# 258Verbos.net
KiCad netlist of a schematic drawn in EAGLE
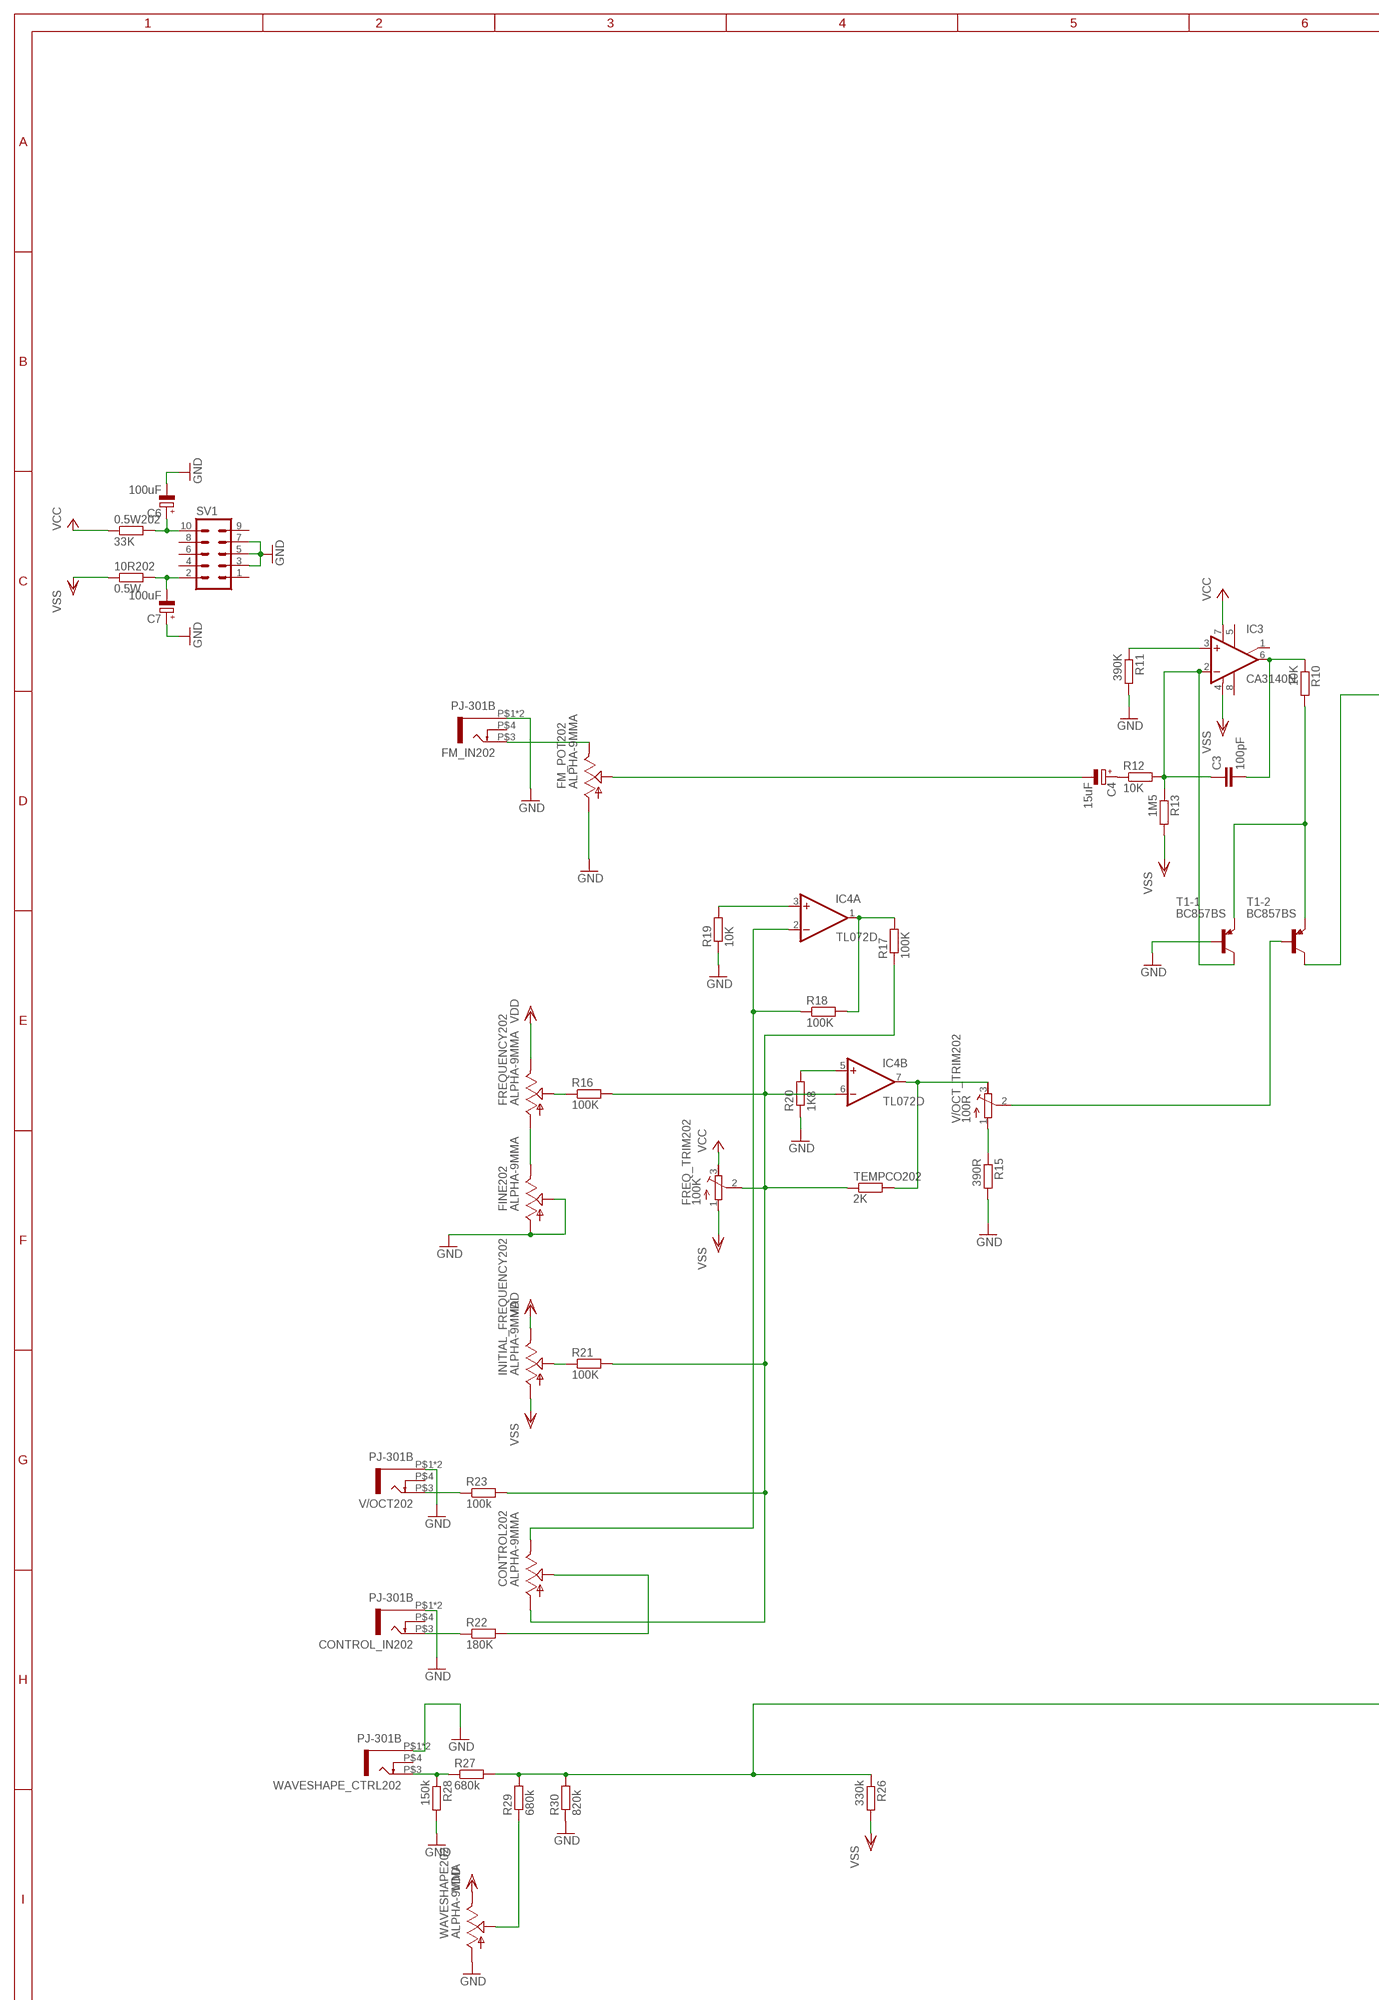
[diagram p0: schematic, sheet 1, part 1 of 2]
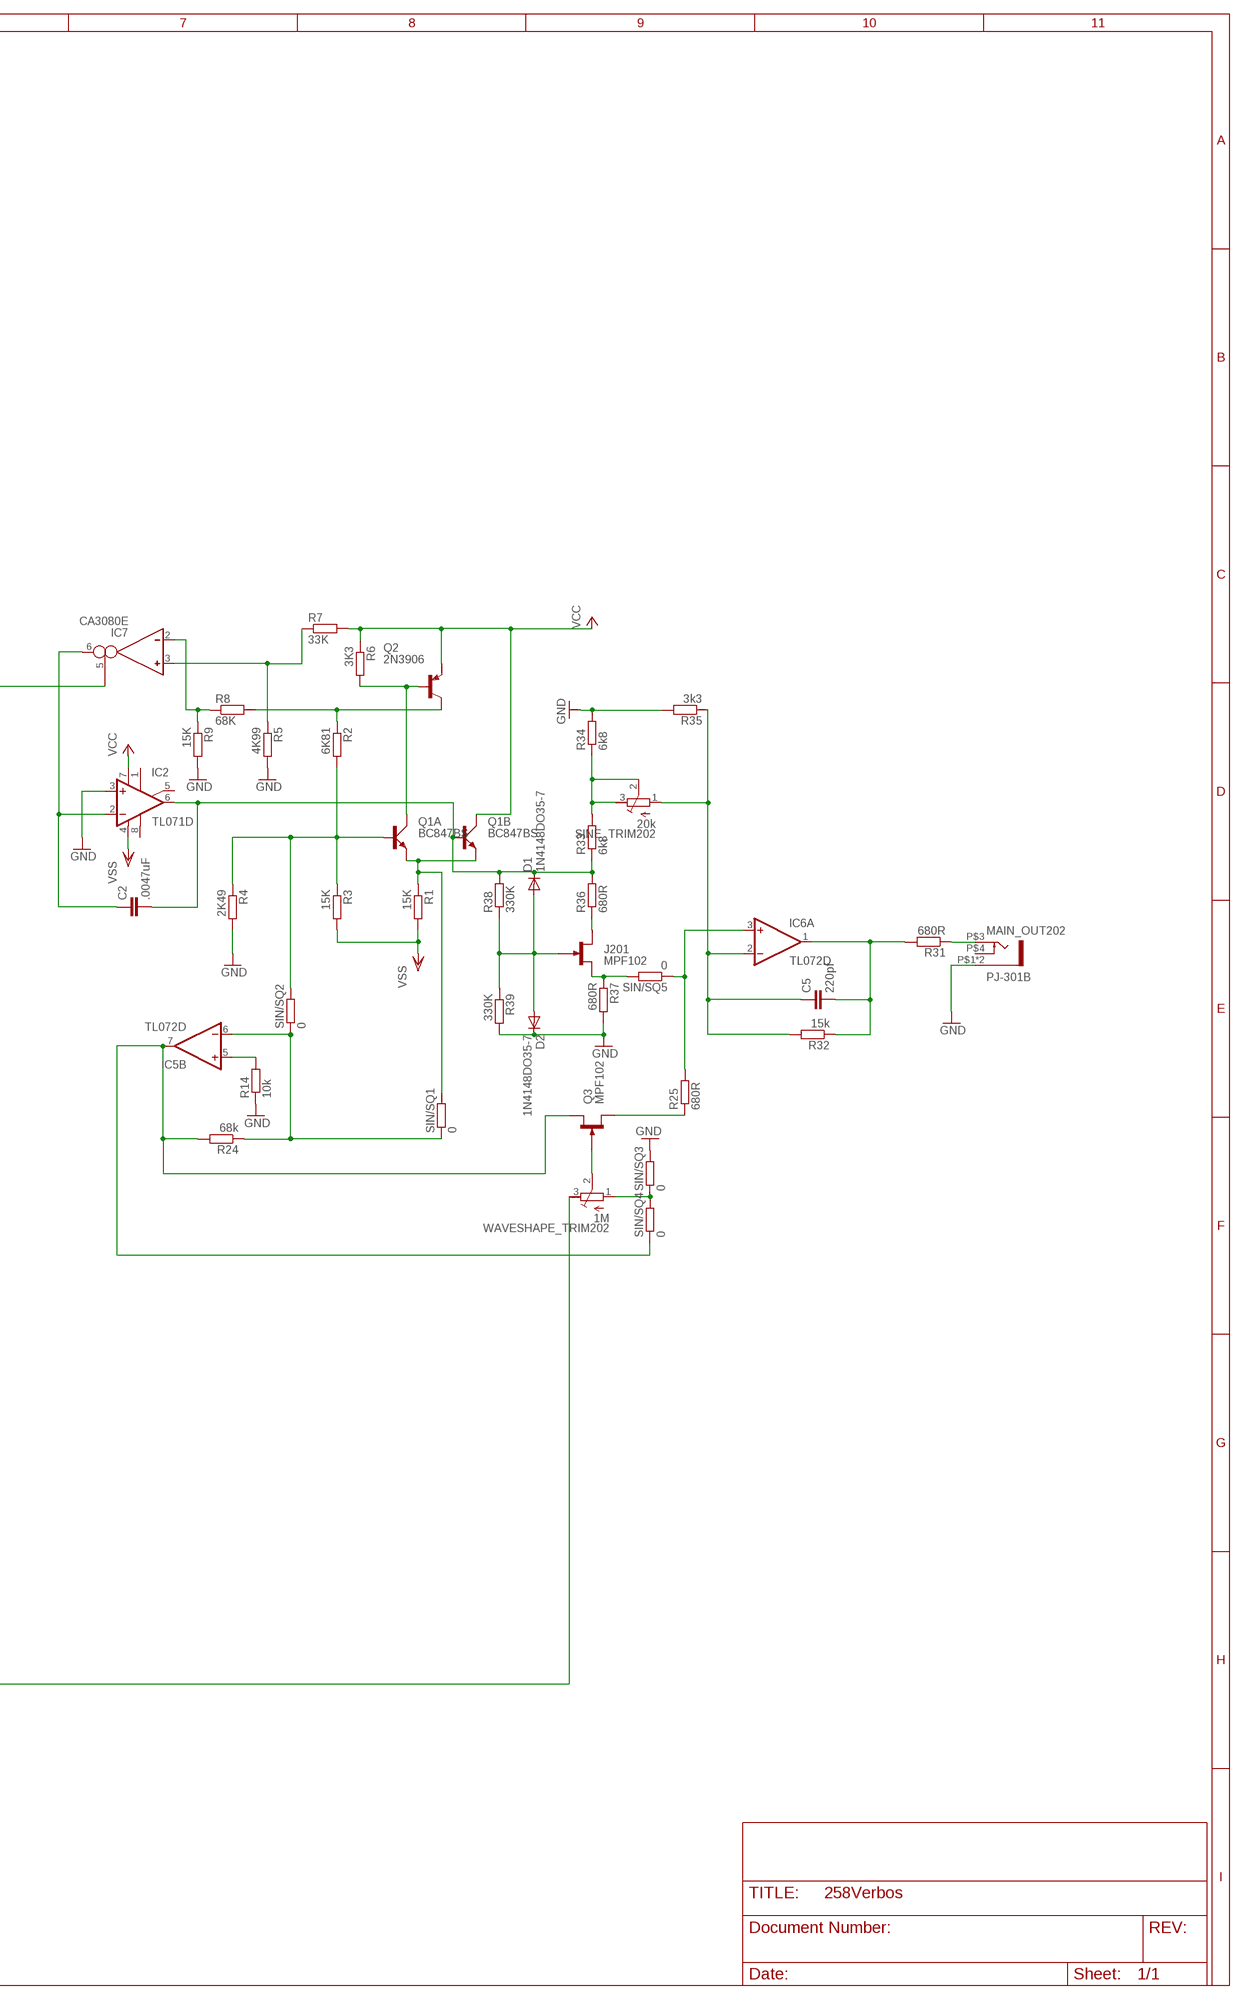
[diagram p1: schematic, sheet 1, part 2 of 2]

(export (version "E")
  (design (tool "Eeschema 10.0.6"))
  (components
    (comp (ref "0.5W202")
      (value "33K")
      (footprint "eagle-import:R0805")
      (libsource (lib "eagle-import") (part "R-EU_R0805"))
    )
    (comp (ref "10R202")
      (value "0.5W")
      (footprint "eagle-import:R0805")
      (libsource (lib "eagle-import") (part "R-EU_R0805"))
    )
    (comp (ref "C2")
      (value ".0047uF")
      (footprint "eagle-import:C5B4.5")
      (libsource (lib "eagle-import") (part "C5/4.5"))
    )
    (comp (ref "C3")
      (value "100pF")
      (footprint "eagle-import:C2.5-3")
      (libsource (lib "eagle-import") (part "C2,5-3"))
    )
    (comp (ref "C4")
      (value "15uF")
      (footprint "eagle-import:E2,5-6E")
      (libsource (lib "eagle-import") (part "CPOL-EUE2,5-6E"))
    )
    (comp (ref "C5")
      (value "220pf")
      (footprint "eagle-import:C2.5-3")
      (libsource (lib "eagle-import") (part "C2,5-3"))
    )
    (comp (ref "C6")
      (value "100uF")
      (footprint "eagle-import:E2,5-6E")
      (libsource (lib "eagle-import") (part "CPOL-EUE2,5-6E"))
    )
    (comp (ref "C7")
      (value "100uF")
      (footprint "eagle-import:E2,5-6E")
      (libsource (lib "eagle-import") (part "CPOL-EUE2,5-6E"))
    )
    (comp (ref "CONTROL202")
      (value "ALPHA-9MMA")
      (footprint "eagle-import:EVUF")
      (libsource (lib "eagle-import") (part "ALPHA-9MMA"))
    )
    (comp (ref "CONTROL_IN202")
      (value "PJ-301B")
      (footprint "eagle-import:PJ-301B")
      (libsource (lib "eagle-import") (part "PJ-301B"))
    )
    (comp (ref "D1")
      (value "1N4148DO35-7")
      (footprint "eagle-import:DO35-7")
      (libsource (lib "eagle-import") (part "1N4148DO35-7"))
    )
    (comp (ref "D2")
      (value "1N4148DO35-7")
      (footprint "eagle-import:DO35-7")
      (libsource (lib "eagle-import") (part "1N4148DO35-7"))
    )
    (comp (ref "FINE202")
      (value "ALPHA-9MMA")
      (footprint "eagle-import:EVUF")
      (libsource (lib "eagle-import") (part "ALPHA-9MMA"))
    )
    (comp (ref "FM_IN202")
      (value "PJ-301B")
      (footprint "eagle-import:PJ-301B")
      (libsource (lib "eagle-import") (part "PJ-301B"))
    )
    (comp (ref "FM_POT202")
      (value "ALPHA-9MMA")
      (footprint "eagle-import:EVUF")
      (libsource (lib "eagle-import") (part "ALPHA-9MMA"))
    )
    (comp (ref "FREQUENCY202")
      (value "ALPHA-9MMA")
      (footprint "eagle-import:EVUF")
      (libsource (lib "eagle-import") (part "ALPHA-9MMA"))
    )
    (comp (ref "FREQ_TRIM202")
      (value "100K")
      (footprint "eagle-import:RTRIM64W")
      (libsource (lib "eagle-import") (part "R-TRIMM64W"))
    )
    (comp (ref "IC2")
      (value "TL071D")
      (footprint "eagle-import:SO08")
      (libsource (lib "eagle-import") (part "TL071D"))
    )
    (comp (ref "IC3")
      (value "CA3140N")
      (footprint "eagle-import:DIL08")
      (libsource (lib "eagle-import") (part "CA3140N"))
    )
    (comp (ref "IC4")
      (value "TL072D")
      (footprint "eagle-import:SO08")
      (libsource (lib "eagle-import") (part "TL072D"))
    )
    (comp (ref "IC5")
      (value "TL072D")
      (footprint "eagle-import:SO08")
      (libsource (lib "eagle-import") (part "TL072D"))
    )
    (comp (ref "IC6")
      (value "TL072D")
      (footprint "eagle-import:SO08")
      (libsource (lib "eagle-import") (part "TL072D"))
    )
    (comp (ref "IC7")
      (value "CA3080E")
      (footprint "eagle-import:DIL08")
      (libsource (lib "eagle-import") (part "CA3080E"))
    )
    (comp (ref "INITIAL_FREQUENCY202")
      (value "ALPHA-9MMA")
      (footprint "eagle-import:EVUF")
      (libsource (lib "eagle-import") (part "ALPHA-9MMA"))
    )
    (comp (ref "J201")
      (value "MPF102")
      (footprint "eagle-import:TO92F")
      (libsource (lib "eagle-import") (part "MPF102"))
    )
    (comp (ref "MAIN_OUT202")
      (value "PJ-301B")
      (footprint "eagle-import:PJ-301B")
      (libsource (lib "eagle-import") (part "PJ-301B"))
    )
    (comp (ref "Q1")
      (value "BC847BS")
      (footprint "eagle-import:SOT363_PHILIPS")
      (libsource (lib "eagle-import") (part "BC847BS"))
    )
    (comp (ref "Q2")
      (value "2N3906")
      (footprint "eagle-import:TO92")
      (libsource (lib "eagle-import") (part "2N3906"))
    )
    (comp (ref "Q3")
      (value "MPF102")
      (footprint "eagle-import:TO92F")
      (libsource (lib "eagle-import") (part "MPF102"))
    )
    (comp (ref "R1")
      (value "15K")
      (footprint "eagle-import:R0805")
      (libsource (lib "eagle-import") (part "R-EU_R0805"))
    )
    (comp (ref "R2")
      (value "6K81")
      (footprint "eagle-import:R0805")
      (libsource (lib "eagle-import") (part "R-EU_R0805"))
    )
    (comp (ref "R3")
      (value "15K")
      (footprint "eagle-import:R0805")
      (libsource (lib "eagle-import") (part "R-EU_R0805"))
    )
    (comp (ref "R4")
      (value "2K49")
      (footprint "eagle-import:R0805")
      (libsource (lib "eagle-import") (part "R-EU_R0805"))
    )
    (comp (ref "R5")
      (value "4K99")
      (footprint "eagle-import:R0805")
      (libsource (lib "eagle-import") (part "R-EU_R0805"))
    )
    (comp (ref "R6")
      (value "3K3")
      (footprint "eagle-import:R0805")
      (libsource (lib "eagle-import") (part "R-EU_R0805"))
    )
    (comp (ref "R7")
      (value "33K")
      (footprint "eagle-import:R0805")
      (libsource (lib "eagle-import") (part "R-EU_R0805"))
    )
    (comp (ref "R8")
      (value "68K")
      (footprint "eagle-import:R0805")
      (libsource (lib "eagle-import") (part "R-EU_R0805"))
    )
    (comp (ref "R9")
      (value "15K")
      (footprint "eagle-import:R0805")
      (libsource (lib "eagle-import") (part "R-EU_R0805"))
    )
    (comp (ref "R10")
      (value "10K")
      (footprint "eagle-import:R0805")
      (libsource (lib "eagle-import") (part "R-EU_R0805"))
    )
    (comp (ref "R11")
      (value "390K")
      (footprint "eagle-import:R0805")
      (libsource (lib "eagle-import") (part "R-EU_R0805"))
    )
    (comp (ref "R12")
      (value "10K")
      (footprint "eagle-import:R0805")
      (libsource (lib "eagle-import") (part "R-EU_R0805"))
    )
    (comp (ref "R13")
      (value "1M5")
      (footprint "eagle-import:R0805")
      (libsource (lib "eagle-import") (part "R-EU_R0805"))
    )
    (comp (ref "R14")
      (value "10k")
      (footprint "eagle-import:R0805")
      (libsource (lib "eagle-import") (part "R-EU_R0805"))
    )
    (comp (ref "R15")
      (value "390R")
      (footprint "eagle-import:R0805")
      (libsource (lib "eagle-import") (part "R-EU_R0805"))
    )
    (comp (ref "R16")
      (value "100K")
      (footprint "eagle-import:R0805")
      (libsource (lib "eagle-import") (part "R-EU_R0805"))
    )
    (comp (ref "R17")
      (value "100K")
      (footprint "eagle-import:R0805")
      (libsource (lib "eagle-import") (part "R-EU_R0805"))
    )
    (comp (ref "R18")
      (value "100K")
      (footprint "eagle-import:R0805")
      (libsource (lib "eagle-import") (part "R-EU_R0805"))
    )
    (comp (ref "R19")
      (value "10K")
      (footprint "eagle-import:R0805")
      (libsource (lib "eagle-import") (part "R-EU_R0805"))
    )
    (comp (ref "R20")
      (value "1K8")
      (footprint "eagle-import:R0805")
      (libsource (lib "eagle-import") (part "R-EU_R0805"))
    )
    (comp (ref "R21")
      (value "100K")
      (footprint "eagle-import:R0805")
      (libsource (lib "eagle-import") (part "R-EU_R0805"))
    )
    (comp (ref "R22")
      (value "180K")
      (footprint "eagle-import:R0805")
      (libsource (lib "eagle-import") (part "R-EU_R0805"))
    )
    (comp (ref "R23")
      (value "100k")
      (footprint "eagle-import:R0805")
      (libsource (lib "eagle-import") (part "R-EU_R0805"))
    )
    (comp (ref "R24")
      (value "68k")
      (footprint "eagle-import:R0805")
      (libsource (lib "eagle-import") (part "R-EU_R0805"))
    )
    (comp (ref "R25")
      (value "680R")
      (footprint "eagle-import:R0805")
      (libsource (lib "eagle-import") (part "R-EU_R0805"))
    )
    (comp (ref "R26")
      (value "330k")
      (footprint "eagle-import:R0805")
      (libsource (lib "eagle-import") (part "R-EU_R0805"))
    )
    (comp (ref "R27")
      (value "680k")
      (footprint "eagle-import:R0805")
      (libsource (lib "eagle-import") (part "R-EU_R0805"))
    )
    (comp (ref "R28")
      (value "150k")
      (footprint "eagle-import:R0805")
      (libsource (lib "eagle-import") (part "R-EU_R0805"))
    )
    (comp (ref "R29")
      (value "680k")
      (footprint "eagle-import:R0805")
      (libsource (lib "eagle-import") (part "R-EU_R0805"))
    )
    (comp (ref "R30")
      (value "820k")
      (footprint "eagle-import:R0805")
      (libsource (lib "eagle-import") (part "R-EU_R0805"))
    )
    (comp (ref "R31")
      (value "680R")
      (footprint "eagle-import:R0805")
      (libsource (lib "eagle-import") (part "R-EU_R0805"))
    )
    (comp (ref "R32")
      (value "15k")
      (footprint "eagle-import:R0805")
      (libsource (lib "eagle-import") (part "R-EU_R0805"))
    )
    (comp (ref "R33")
      (value "6k8")
      (footprint "eagle-import:R0805")
      (libsource (lib "eagle-import") (part "R-EU_R0805"))
    )
    (comp (ref "R34")
      (value "6k8")
      (footprint "eagle-import:R0805")
      (libsource (lib "eagle-import") (part "R-EU_R0805"))
    )
    (comp (ref "R35")
      (value "3k3")
      (footprint "eagle-import:R0805")
      (libsource (lib "eagle-import") (part "R-EU_R0805"))
    )
    (comp (ref "R36")
      (value "680R")
      (footprint "eagle-import:R0805")
      (libsource (lib "eagle-import") (part "R-EU_R0805"))
    )
    (comp (ref "R37")
      (value "680R")
      (footprint "eagle-import:R0805")
      (libsource (lib "eagle-import") (part "R-EU_R0805"))
    )
    (comp (ref "R38")
      (value "330K")
      (footprint "eagle-import:R0805")
      (libsource (lib "eagle-import") (part "R-EU_R0805"))
    )
    (comp (ref "R39")
      (value "330K")
      (footprint "eagle-import:R0805")
      (libsource (lib "eagle-import") (part "R-EU_R0805"))
    )
    (comp (ref "SIN/SQ1")
      (value "0")
      (footprint "eagle-import:R0805")
      (libsource (lib "eagle-import") (part "R-EU_R0805"))
    )
    (comp (ref "SIN/SQ2")
      (value "0")
      (footprint "eagle-import:R0805")
      (libsource (lib "eagle-import") (part "R-EU_R0805"))
    )
    (comp (ref "SIN/SQ3")
      (value "0")
      (footprint "eagle-import:R0805")
      (libsource (lib "eagle-import") (part "R-EU_R0805"))
    )
    (comp (ref "SIN/SQ4")
      (value "0")
      (footprint "eagle-import:R0805")
      (libsource (lib "eagle-import") (part "R-EU_R0805"))
    )
    (comp (ref "SIN/SQ5")
      (value "0")
      (footprint "eagle-import:R0805")
      (libsource (lib "eagle-import") (part "R-EU_R0805"))
    )
    (comp (ref "SINE_TRIM202")
      (value "20k")
      (footprint "eagle-import:RTRIM64W")
      (libsource (lib "eagle-import") (part "R-TRIMM64W"))
    )
    (comp (ref "SV1")
      (value "10_PIN_HEADER")
      (footprint "eagle-import:MA05-2")
      (libsource (lib "eagle-import") (part "10_PIN_HEADER"))
    )
    (comp (ref "T1")
      (value "BC857BS")
      (footprint "eagle-import:SOT363")
      (libsource (lib "eagle-import") (part "BC857BS"))
    )
    (comp (ref "TEMPCO202")
      (value "2K")
      (footprint "eagle-import:R0805")
      (libsource (lib "eagle-import") (part "R-EU_R0805"))
    )
    (comp (ref "V/OCT202")
      (value "PJ-301B")
      (footprint "eagle-import:PJ-301B")
      (libsource (lib "eagle-import") (part "PJ-301B"))
    )
    (comp (ref "V/OCT_TRIM202")
      (value "100R")
      (footprint "eagle-import:RTRIM64W")
      (libsource (lib "eagle-import") (part "R-TRIMM64W"))
    )
    (comp (ref "WAVESHAPE202")
      (value "ALPHA-9MMA")
      (footprint "eagle-import:EVUF")
      (libsource (lib "eagle-import") (part "ALPHA-9MMA"))
    )
    (comp (ref "WAVESHAPE_CTRL202")
      (value "PJ-301B")
      (footprint "eagle-import:PJ-301B")
      (libsource (lib "eagle-import") (part "PJ-301B"))
    )
    (comp (ref "WAVESHAPE_TRIM202")
      (value "1M")
      (footprint "eagle-import:RTRIM64W")
      (libsource (lib "eagle-import") (part "R-TRIMM64W"))
    )
  )
  (nets
    (net (code "1") (name "GND") (class "Default")
      (node (ref "C6") (pin "-") (pinfunction "-_-") (pintype "passive"))
      (node (ref "C7") (pin "+") (pinfunction "+_+") (pintype "passive"))
      (node (ref "CONTROL_IN202") (pin "P$1") (pinfunction "5_P$1") (pintype "passive"))
      (node (ref "CONTROL_IN202") (pin "P$2") (pinfunction "5_P$2") (pintype "passive"))
      (node (ref "D2") (pin "C") (pinfunction "C_C") (pintype "passive"))
      (node (ref "FINE202") (pin "1") (pinfunction "A_1") (pintype "passive"))
      (node (ref "FINE202") (pin "2") (pinfunction "S_2") (pintype "passive"))
      (node (ref "FM_IN202") (pin "P$1") (pinfunction "5_P$1") (pintype "passive"))
      (node (ref "FM_IN202") (pin "P$2") (pinfunction "5_P$2") (pintype "passive"))
      (node (ref "FM_POT202") (pin "1") (pinfunction "A_1") (pintype "passive"))
      (node (ref "IC2") (pin "3") (pinfunction "+IN_3") (pintype "input"))
      (node (ref "MAIN_OUT202") (pin "P$1") (pinfunction "5_P$1") (pintype "passive"))
      (node (ref "MAIN_OUT202") (pin "P$2") (pinfunction "5_P$2") (pintype "passive"))
      (node (ref "R11") (pin "2") (pinfunction "2_2") (pintype "passive"))
      (node (ref "R14") (pin "1") (pinfunction "1_1") (pintype "passive"))
      (node (ref "R15") (pin "2") (pinfunction "2_2") (pintype "passive"))
      (node (ref "R19") (pin "1") (pinfunction "1_1") (pintype "passive"))
      (node (ref "R20") (pin "1") (pinfunction "1_1") (pintype "passive"))
      (node (ref "R28") (pin "2") (pinfunction "2_2") (pintype "passive"))
      (node (ref "R30") (pin "1") (pinfunction "1_1") (pintype "passive"))
      (node (ref "R34") (pin "2") (pinfunction "2_2") (pintype "passive"))
      (node (ref "R35") (pin "2") (pinfunction "2_2") (pintype "passive"))
      (node (ref "R37") (pin "2") (pinfunction "2_2") (pintype "passive"))
      (node (ref "R39") (pin "2") (pinfunction "2_2") (pintype "passive"))
      (node (ref "R4") (pin "2") (pinfunction "2_2") (pintype "passive"))
      (node (ref "R5") (pin "2") (pinfunction "2_2") (pintype "passive"))
      (node (ref "R9") (pin "2") (pinfunction "2_2") (pintype "passive"))
      (node (ref "SIN/SQ3") (pin "2") (pinfunction "2_2") (pintype "passive"))
      (node (ref "SV1") (pin "3") (pinfunction "3_3") (pintype "passive"))
      (node (ref "SV1") (pin "5") (pinfunction "5_5") (pintype "passive"))
      (node (ref "SV1") (pin "7") (pinfunction "7_7") (pintype "passive"))
      (node (ref "T1") (pin "2") (pinfunction "B_2") (pintype "passive"))
      (node (ref "V/OCT202") (pin "P$1") (pinfunction "5_P$1") (pintype "passive"))
      (node (ref "V/OCT202") (pin "P$2") (pinfunction "5_P$2") (pintype "passive"))
      (node (ref "WAVESHAPE202") (pin "1") (pinfunction "A_1") (pintype "passive"))
      (node (ref "WAVESHAPE_CTRL202") (pin "P$1") (pinfunction "5_P$1") (pintype "passive"))
      (node (ref "WAVESHAPE_CTRL202") (pin "P$2") (pinfunction "5_P$2") (pintype "passive"))
    )
    (net (code "2") (name "Net-(0.5W202-Pad2)") (class "Default")
      (node (ref "0.5W202") (pin "2") (pinfunction "2_2") (pintype "passive"))
      (node (ref "C6") (pin "+") (pinfunction "+_+") (pintype "passive"))
      (node (ref "SV1") (pin "10") (pinfunction "10_10") (pintype "passive"))
    )
    (net (code "3") (name "Net-(10R202-Pad2)") (class "Default")
      (node (ref "10R202") (pin "2") (pinfunction "2_2") (pintype "passive"))
      (node (ref "C7") (pin "-") (pinfunction "-_-") (pintype "passive"))
      (node (ref "SV1") (pin "2") (pinfunction "2_2") (pintype "passive"))
    )
    (net (code "4") (name "Net-(C4-Pad+)") (class "Default")
      (node (ref "C4") (pin "+") (pinfunction "+_+") (pintype "passive"))
      (node (ref "R12") (pin "1") (pinfunction "1_1") (pintype "passive"))
    )
    (net (code "5") (name "Net-(CONTROL202-A)") (class "Default")
      (node (ref "CONTROL202") (pin "1") (pinfunction "A_1") (pintype "passive"))
      (node (ref "FREQ_TRIM202") (pin "2") (pinfunction "S_2") (pintype "passive"))
      (node (ref "IC4") (pin "6") (pinfunction "-IN_6") (pintype "input"))
      (node (ref "R16") (pin "2") (pinfunction "2_2") (pintype "passive"))
      (node (ref "R17") (pin "1") (pinfunction "1_1") (pintype "passive"))
      (node (ref "R21") (pin "2") (pinfunction "2_2") (pintype "passive"))
      (node (ref "R23") (pin "2") (pinfunction "2_2") (pintype "passive"))
      (node (ref "TEMPCO202") (pin "1") (pinfunction "1_1") (pintype "passive"))
    )
    (net (code "6") (name "Net-(CONTROL202-E)") (class "Default")
      (node (ref "CONTROL202") (pin "3") (pinfunction "E_3") (pintype "passive"))
      (node (ref "IC4") (pin "2") (pinfunction "-IN_2") (pintype "input"))
      (node (ref "R18") (pin "1") (pinfunction "1_1") (pintype "passive"))
    )
    (net (code "7") (name "Net-(CONTROL202-S)") (class "Default")
      (node (ref "CONTROL202") (pin "2") (pinfunction "S_2") (pintype "passive"))
      (node (ref "R22") (pin "2") (pinfunction "2_2") (pintype "passive"))
    )
    (net (code "8") (name "Net-(CONTROL_IN202-3)") (class "Default")
      (node (ref "CONTROL_IN202") (pin "P$3") (pinfunction "3_P$3") (pintype "passive"))
      (node (ref "R22") (pin "1") (pinfunction "1_1") (pintype "passive"))
    )
    (net (code "9") (name "Net-(FINE202-E)") (class "Default")
      (node (ref "FINE202") (pin "3") (pinfunction "E_3") (pintype "passive"))
      (node (ref "FREQUENCY202") (pin "1") (pinfunction "A_1") (pintype "passive"))
    )
    (net (code "10") (name "Net-(FM_IN202-3)") (class "Default")
      (node (ref "FM_IN202") (pin "P$3") (pinfunction "3_P$3") (pintype "passive"))
      (node (ref "FM_POT202") (pin "3") (pinfunction "E_3") (pintype "passive"))
    )
    (net (code "11") (name "Net-(FM_POT202-S)") (class "Default")
      (node (ref "C4") (pin "-") (pinfunction "-_-") (pintype "passive"))
      (node (ref "FM_POT202") (pin "2") (pinfunction "S_2") (pintype "passive"))
    )
    (net (code "12") (name "Net-(FREQUENCY202-S)") (class "Default")
      (node (ref "FREQUENCY202") (pin "2") (pinfunction "S_2") (pintype "passive"))
      (node (ref "R16") (pin "1") (pinfunction "1_1") (pintype "passive"))
    )
    (net (code "13") (name "Net-(IC2--IN)") (class "Default")
      (node (ref "C2") (pin "1") (pinfunction "1_1") (pintype "passive"))
      (node (ref "IC2") (pin "2") (pinfunction "-IN_2") (pintype "input"))
      (node (ref "IC7") (pin "6") (pinfunction "OUT_6") (pintype "output"))
    )
    (net (code "14") (name "Net-(IC2-OUT)") (class "Default")
      (node (ref "C2") (pin "2") (pinfunction "2_2") (pintype "passive"))
      (node (ref "D1") (pin "C") (pinfunction "C_C") (pintype "passive"))
      (node (ref "IC2") (pin "6") (pinfunction "OUT_6") (pintype "output"))
      (node (ref "Q1") (pin "5") (pinfunction "B_5") (pintype "passive"))
      (node (ref "R33") (pin "1") (pinfunction "1_1") (pintype "passive"))
      (node (ref "R36") (pin "2") (pinfunction "2_2") (pintype "passive"))
      (node (ref "R38") (pin "2") (pinfunction "2_2") (pintype "passive"))
    )
    (net (code "15") (name "Net-(IC3-+IN)") (class "Default")
      (node (ref "IC3") (pin "3") (pinfunction "+IN_3") (pintype "input"))
      (node (ref "R11") (pin "1") (pinfunction "1_1") (pintype "passive"))
    )
    (net (code "16") (name "Net-(IC3--IN)") (class "Default")
      (node (ref "C3") (pin "1") (pinfunction "1_1") (pintype "passive"))
      (node (ref "IC3") (pin "2") (pinfunction "-IN_2") (pintype "input"))
      (node (ref "R12") (pin "2") (pinfunction "2_2") (pintype "passive"))
      (node (ref "R13") (pin "1") (pinfunction "1_1") (pintype "passive"))
      (node (ref "T1") (pin "6") (pinfunction "C_6") (pintype "passive"))
    )
    (net (code "17") (name "Net-(IC3-OUT)") (class "Default")
      (node (ref "C3") (pin "2") (pinfunction "2_2") (pintype "passive"))
      (node (ref "IC3") (pin "6") (pinfunction "OUT_6") (pintype "output"))
      (node (ref "R10") (pin "1") (pinfunction "1_1") (pintype "passive"))
    )
    (net (code "18") (name "Net-(IC4A-+IN)") (class "Default")
      (node (ref "IC4") (pin "3") (pinfunction "+IN_3") (pintype "input"))
      (node (ref "R19") (pin "2") (pinfunction "2_2") (pintype "passive"))
    )
    (net (code "19") (name "Net-(IC4A-OUT)") (class "Default")
      (node (ref "IC4") (pin "1") (pinfunction "OUT_1") (pintype "output"))
      (node (ref "R17") (pin "2") (pinfunction "2_2") (pintype "passive"))
      (node (ref "R18") (pin "2") (pinfunction "2_2") (pintype "passive"))
    )
    (net (code "20") (name "Net-(IC4B-+IN)") (class "Default")
      (node (ref "IC4") (pin "5") (pinfunction "+IN_5") (pintype "input"))
      (node (ref "R20") (pin "2") (pinfunction "2_2") (pintype "passive"))
    )
    (net (code "21") (name "Net-(IC4B-OUT)") (class "Default")
      (node (ref "IC4") (pin "7") (pinfunction "OUT_7") (pintype "output"))
      (node (ref "TEMPCO202") (pin "2") (pinfunction "2_2") (pintype "passive"))
      (node (ref "V/OCT_TRIM202") (pin "3") (pinfunction "E_3") (pintype "passive"))
    )
    (net (code "22") (name "Net-(IC5B-+IN)") (class "Default")
      (node (ref "IC5") (pin "5") (pinfunction "+IN_5") (pintype "input"))
      (node (ref "R14") (pin "2") (pinfunction "2_2") (pintype "passive"))
    )
    (net (code "23") (name "Net-(IC5B--IN)") (class "Default")
      (node (ref "IC5") (pin "6") (pinfunction "-IN_6") (pintype "input"))
      (node (ref "R24") (pin "1") (pinfunction "1_1") (pintype "passive"))
      (node (ref "SIN/SQ1") (pin "1") (pinfunction "1_1") (pintype "passive"))
      (node (ref "SIN/SQ2") (pin "1") (pinfunction "1_1") (pintype "passive"))
    )
    (net (code "24") (name "Net-(IC5B-OUT)") (class "Default")
      (node (ref "IC5") (pin "7") (pinfunction "OUT_7") (pintype "output"))
      (node (ref "Q3") (pin "1") (pinfunction "D_1") (pintype "passive"))
      (node (ref "R24") (pin "2") (pinfunction "2_2") (pintype "passive"))
      (node (ref "SIN/SQ4") (pin "1") (pinfunction "1_1") (pintype "passive"))
    )
    (net (code "25") (name "Net-(IC6A-+IN)") (class "Default")
      (node (ref "IC6") (pin "3") (pinfunction "+IN_3") (pintype "input"))
      (node (ref "R25") (pin "2") (pinfunction "2_2") (pintype "passive"))
      (node (ref "SIN/SQ5") (pin "1") (pinfunction "1_1") (pintype "passive"))
    )
    (net (code "26") (name "Net-(IC6A--IN)") (class "Default")
      (node (ref "C5") (pin "1") (pinfunction "1_1") (pintype "passive"))
      (node (ref "IC6") (pin "2") (pinfunction "-IN_2") (pintype "input"))
      (node (ref "R32") (pin "2") (pinfunction "2_2") (pintype "passive"))
      (node (ref "R35") (pin "1") (pinfunction "1_1") (pintype "passive"))
      (node (ref "SINE_TRIM202") (pin "1") (pinfunction "A_1") (pintype "passive"))
    )
    (net (code "27") (name "Net-(IC6A-OUT)") (class "Default")
      (node (ref "C5") (pin "2") (pinfunction "2_2") (pintype "passive"))
      (node (ref "IC6") (pin "1") (pinfunction "OUT_1") (pintype "output"))
      (node (ref "R31") (pin "2") (pinfunction "2_2") (pintype "passive"))
      (node (ref "R32") (pin "1") (pinfunction "1_1") (pintype "passive"))
    )
    (net (code "28") (name "Net-(IC7A-IN_N)") (class "Default")
      (node (ref "IC7") (pin "2") (pinfunction "IN_N_2") (pintype "input"))
      (node (ref "R8") (pin "1") (pinfunction "1_1") (pintype "passive"))
      (node (ref "R9") (pin "1") (pinfunction "1_1") (pintype "passive"))
    )
    (net (code "29") (name "Net-(IC7A-IN_P)") (class "Default")
      (node (ref "IC7") (pin "3") (pinfunction "IN_P_3") (pintype "input"))
      (node (ref "R5") (pin "1") (pinfunction "1_1") (pintype "passive"))
      (node (ref "R7") (pin "1") (pinfunction "1_1") (pintype "passive"))
    )
    (net (code "30") (name "Net-(IC7A-I_BIAS)") (class "Default")
      (node (ref "IC7") (pin "5") (pinfunction "I_BIAS_5") (pintype "input"))
      (node (ref "T1") (pin "3") (pinfunction "C_3") (pintype "passive"))
    )
    (net (code "31") (name "Net-(INITIAL_FREQUENCY202-S)") (class "Default")
      (node (ref "INITIAL_FREQUENCY202") (pin "2") (pinfunction "S_2") (pintype "passive"))
      (node (ref "R21") (pin "1") (pinfunction "1_1") (pintype "passive"))
    )
    (net (code "32") (name "Net-(J201-D)") (class "Default")
      (node (ref "J201") (pin "1") (pinfunction "D_1") (pintype "passive"))
      (node (ref "R36") (pin "1") (pinfunction "1_1") (pintype "passive"))
    )
    (net (code "33") (name "Net-(J201-G)") (class "Default")
      (node (ref "D1") (pin "A") (pinfunction "A_A") (pintype "passive"))
      (node (ref "D2") (pin "A") (pinfunction "A_A") (pintype "passive"))
      (node (ref "J201") (pin "3") (pinfunction "G_3") (pintype "passive"))
      (node (ref "R38") (pin "1") (pinfunction "1_1") (pintype "passive"))
      (node (ref "R39") (pin "1") (pinfunction "1_1") (pintype "passive"))
    )
    (net (code "34") (name "Net-(J201-S)") (class "Default")
      (node (ref "J201") (pin "2") (pinfunction "S_2") (pintype "passive"))
      (node (ref "R37") (pin "1") (pinfunction "1_1") (pintype "passive"))
      (node (ref "SIN/SQ5") (pin "2") (pinfunction "2_2") (pintype "passive"))
    )
    (net (code "35") (name "Net-(MAIN_OUT202-3)") (class "Default")
      (node (ref "MAIN_OUT202") (pin "P$3") (pinfunction "3_P$3") (pintype "passive"))
      (node (ref "R31") (pin "1") (pinfunction "1_1") (pintype "passive"))
    )
    (net (code "36") (name "Net-(Q1A-B)") (class "Default")
      (node (ref "Q1") (pin "2") (pinfunction "B_2") (pintype "passive"))
      (node (ref "R2") (pin "2") (pinfunction "2_2") (pintype "passive"))
      (node (ref "R3") (pin "1") (pinfunction "1_1") (pintype "passive"))
      (node (ref "R4") (pin "1") (pinfunction "1_1") (pintype "passive"))
      (node (ref "SIN/SQ2") (pin "2") (pinfunction "2_2") (pintype "passive"))
    )
    (net (code "37") (name "Net-(Q1A-C)") (class "Default")
      (node (ref "Q1") (pin "6") (pinfunction "C_6") (pintype "passive"))
      (node (ref "Q2") (pin "2") (pinfunction "B_2") (pintype "passive"))
      (node (ref "R6") (pin "2") (pinfunction "2_2") (pintype "passive"))
    )
    (net (code "38") (name "Net-(Q1A-E)") (class "Default")
      (node (ref "Q1") (pin "1") (pinfunction "E_1") (pintype "passive"))
      (node (ref "Q1") (pin "4") (pinfunction "E_4") (pintype "passive"))
      (node (ref "R1") (pin "1") (pinfunction "1_1") (pintype "passive"))
      (node (ref "SIN/SQ1") (pin "2") (pinfunction "2_2") (pintype "passive"))
    )
    (net (code "39") (name "Net-(Q2-C)") (class "Default")
      (node (ref "Q2") (pin "1") (pinfunction "C_1") (pintype "passive"))
      (node (ref "R2") (pin "1") (pinfunction "1_1") (pintype "passive"))
      (node (ref "R8") (pin "2") (pinfunction "2_2") (pintype "passive"))
    )
    (net (code "40") (name "Net-(Q3-G)") (class "Default")
      (node (ref "Q3") (pin "3") (pinfunction "G_3") (pintype "passive"))
      (node (ref "WAVESHAPE_TRIM202") (pin "2") (pinfunction "S_2") (pintype "passive"))
    )
    (net (code "41") (name "Net-(Q3-S)") (class "Default")
      (node (ref "Q3") (pin "2") (pinfunction "S_2") (pintype "passive"))
      (node (ref "R25") (pin "1") (pinfunction "1_1") (pintype "passive"))
    )
    (net (code "42") (name "Net-(SINE_TRIM202-E)") (class "Default")
      (node (ref "R33") (pin "2") (pinfunction "2_2") (pintype "passive"))
      (node (ref "R34") (pin "1") (pinfunction "1_1") (pintype "passive"))
      (node (ref "SINE_TRIM202") (pin "2") (pinfunction "S_2") (pintype "passive"))
      (node (ref "SINE_TRIM202") (pin "3") (pinfunction "E_3") (pintype "passive"))
    )
    (net (code "43") (name "Net-(T1A-E)") (class "Default")
      (node (ref "R10") (pin "2") (pinfunction "2_2") (pintype "passive"))
      (node (ref "T1") (pin "1") (pinfunction "E_1") (pintype "passive"))
      (node (ref "T1") (pin "4") (pinfunction "E_4") (pintype "passive"))
    )
    (net (code "44") (name "Net-(T1B-B)") (class "Default")
      (node (ref "T1") (pin "5") (pinfunction "B_5") (pintype "passive"))
      (node (ref "V/OCT_TRIM202") (pin "2") (pinfunction "S_2") (pintype "passive"))
    )
    (net (code "45") (name "Net-(V/OCT202-3)") (class "Default")
      (node (ref "R23") (pin "1") (pinfunction "1_1") (pintype "passive"))
      (node (ref "V/OCT202") (pin "P$3") (pinfunction "3_P$3") (pintype "passive"))
    )
    (net (code "46") (name "Net-(V/OCT_TRIM202-A)") (class "Default")
      (node (ref "R15") (pin "1") (pinfunction "1_1") (pintype "passive"))
      (node (ref "V/OCT_TRIM202") (pin "1") (pinfunction "A_1") (pintype "passive"))
    )
    (net (code "47") (name "Net-(WAVESHAPE202-S)") (class "Default")
      (node (ref "R29") (pin "1") (pinfunction "1_1") (pintype "passive"))
      (node (ref "WAVESHAPE202") (pin "2") (pinfunction "S_2") (pintype "passive"))
    )
    (net (code "48") (name "Net-(WAVESHAPE_CTRL202-3)") (class "Default")
      (node (ref "R27") (pin "1") (pinfunction "1_1") (pintype "passive"))
      (node (ref "R28") (pin "1") (pinfunction "1_1") (pintype "passive"))
      (node (ref "WAVESHAPE_CTRL202") (pin "P$3") (pinfunction "3_P$3") (pintype "passive"))
    )
    (net (code "49") (name "Net-(WAVESHAPE_TRIM202-A)") (class "Default")
      (node (ref "SIN/SQ3") (pin "1") (pinfunction "1_1") (pintype "passive"))
      (node (ref "SIN/SQ4") (pin "2") (pinfunction "2_2") (pintype "passive"))
      (node (ref "WAVESHAPE_TRIM202") (pin "1") (pinfunction "A_1") (pintype "passive"))
    )
    (net (code "50") (name "Net-(WAVESHAPE_TRIM202-E)") (class "Default")
      (node (ref "R26") (pin "1") (pinfunction "1_1") (pintype "passive"))
      (node (ref "R27") (pin "2") (pinfunction "2_2") (pintype "passive"))
      (node (ref "R29") (pin "2") (pinfunction "2_2") (pintype "passive"))
      (node (ref "R30") (pin "2") (pinfunction "2_2") (pintype "passive"))
      (node (ref "WAVESHAPE_TRIM202") (pin "3") (pinfunction "E_3") (pintype "passive"))
    )
    (net (code "51") (name "VCC") (class "Default")
      (node (ref "0.5W202") (pin "1") (pinfunction "1_1") (pintype "passive"))
      (node (ref "FREQ_TRIM202") (pin "3") (pinfunction "E_3") (pintype "passive"))
      (node (ref "IC2") (pin "7") (pinfunction "V+_7") (pintype "power_in"))
      (node (ref "IC3") (pin "7") (pinfunction "V+_7") (pintype "power_in"))
      (node (ref "Q1") (pin "3") (pinfunction "C_3") (pintype "passive"))
      (node (ref "Q2") (pin "3") (pinfunction "E_3") (pintype "passive"))
      (node (ref "R6") (pin "1") (pinfunction "1_1") (pintype "passive"))
      (node (ref "R7") (pin "2") (pinfunction "2_2") (pintype "passive"))
    )
    (net (code "52") (name "VDD") (class "Default")
      (node (ref "FREQUENCY202") (pin "3") (pinfunction "E_3") (pintype "passive"))
      (node (ref "INITIAL_FREQUENCY202") (pin "3") (pinfunction "E_3") (pintype "passive"))
      (node (ref "WAVESHAPE202") (pin "3") (pinfunction "E_3") (pintype "passive"))
    )
    (net (code "53") (name "VSS") (class "Default")
      (node (ref "10R202") (pin "1") (pinfunction "1_1") (pintype "passive"))
      (node (ref "FREQ_TRIM202") (pin "1") (pinfunction "A_1") (pintype "passive"))
      (node (ref "IC2") (pin "4") (pinfunction "V-_4") (pintype "power_in"))
      (node (ref "IC3") (pin "4") (pinfunction "V-_4") (pintype "power_in"))
      (node (ref "INITIAL_FREQUENCY202") (pin "1") (pinfunction "A_1") (pintype "passive"))
      (node (ref "R1") (pin "2") (pinfunction "2_2") (pintype "passive"))
      (node (ref "R13") (pin "2") (pinfunction "2_2") (pintype "passive"))
      (node (ref "R26") (pin "2") (pinfunction "2_2") (pintype "passive"))
      (node (ref "R3") (pin "2") (pinfunction "2_2") (pintype "passive"))
    )
    (net (code "54") (name "unconnected-(CONTROL_IN202-4-PadP$4)") (class "Default")
      (node (ref "CONTROL_IN202") (pin "P$4") (pinfunction "4_P$4") (pintype "passive"))
    )
    (net (code "55") (name "unconnected-(FM_IN202-4-PadP$4)") (class "Default")
      (node (ref "FM_IN202") (pin "P$4") (pinfunction "4_P$4") (pintype "passive"))
    )
    (net (code "56") (name "unconnected-(IC2-ON1-Pad1)") (class "Default")
      (node (ref "IC2") (pin "1") (pinfunction "ON1_1") (pintype "passive"))
    )
    (net (code "57") (name "unconnected-(IC2-ON2-Pad5)") (class "Default")
      (node (ref "IC2") (pin "5") (pinfunction "ON2_5") (pintype "passive"))
    )
    (net (code "58") (name "unconnected-(IC2-OPT-Pad8)") (class "Default")
      (node (ref "IC2") (pin "8") (pinfunction "OPT_8") (pintype "passive"))
    )
    (net (code "59") (name "unconnected-(IC3-CMP-Pad8)") (class "Default")
      (node (ref "IC3") (pin "8") (pinfunction "CMP_8") (pintype "passive"))
    )
    (net (code "60") (name "unconnected-(IC3-ON-Pad5)") (class "Default")
      (node (ref "IC3") (pin "5") (pinfunction "ON_5") (pintype "passive"))
    )
    (net (code "61") (name "unconnected-(IC3-ON{slash}CMP-Pad1)") (class "Default")
      (node (ref "IC3") (pin "1") (pinfunction "ON/CMP_1") (pintype "passive"))
    )
    (net (code "62") (name "unconnected-(MAIN_OUT202-4-PadP$4)") (class "Default")
      (node (ref "MAIN_OUT202") (pin "P$4") (pinfunction "4_P$4") (pintype "passive"))
    )
    (net (code "63") (name "unconnected-(SV1-Pad1)") (class "Default")
      (node (ref "SV1") (pin "1") (pinfunction "1_1") (pintype "passive"))
    )
    (net (code "64") (name "unconnected-(SV1-Pad4)") (class "Default")
      (node (ref "SV1") (pin "4") (pinfunction "4_4") (pintype "passive"))
    )
    (net (code "65") (name "unconnected-(SV1-Pad6)") (class "Default")
      (node (ref "SV1") (pin "6") (pinfunction "6_6") (pintype "passive"))
    )
    (net (code "66") (name "unconnected-(SV1-Pad8)") (class "Default")
      (node (ref "SV1") (pin "8") (pinfunction "8_8") (pintype "passive"))
    )
    (net (code "67") (name "unconnected-(SV1-Pad9)") (class "Default")
      (node (ref "SV1") (pin "9") (pinfunction "9_9") (pintype "passive"))
    )
    (net (code "68") (name "unconnected-(V/OCT202-4-PadP$4)") (class "Default")
      (node (ref "V/OCT202") (pin "P$4") (pinfunction "4_P$4") (pintype "passive"))
    )
    (net (code "69") (name "unconnected-(WAVESHAPE_CTRL202-4-PadP$4)") (class "Default")
      (node (ref "WAVESHAPE_CTRL202") (pin "P$4") (pinfunction "4_P$4") (pintype "passive"))
    )
  )
)
